# transmitter5r_eagle7x.net
KiCad netlist of a schematic drawn in EAGLE
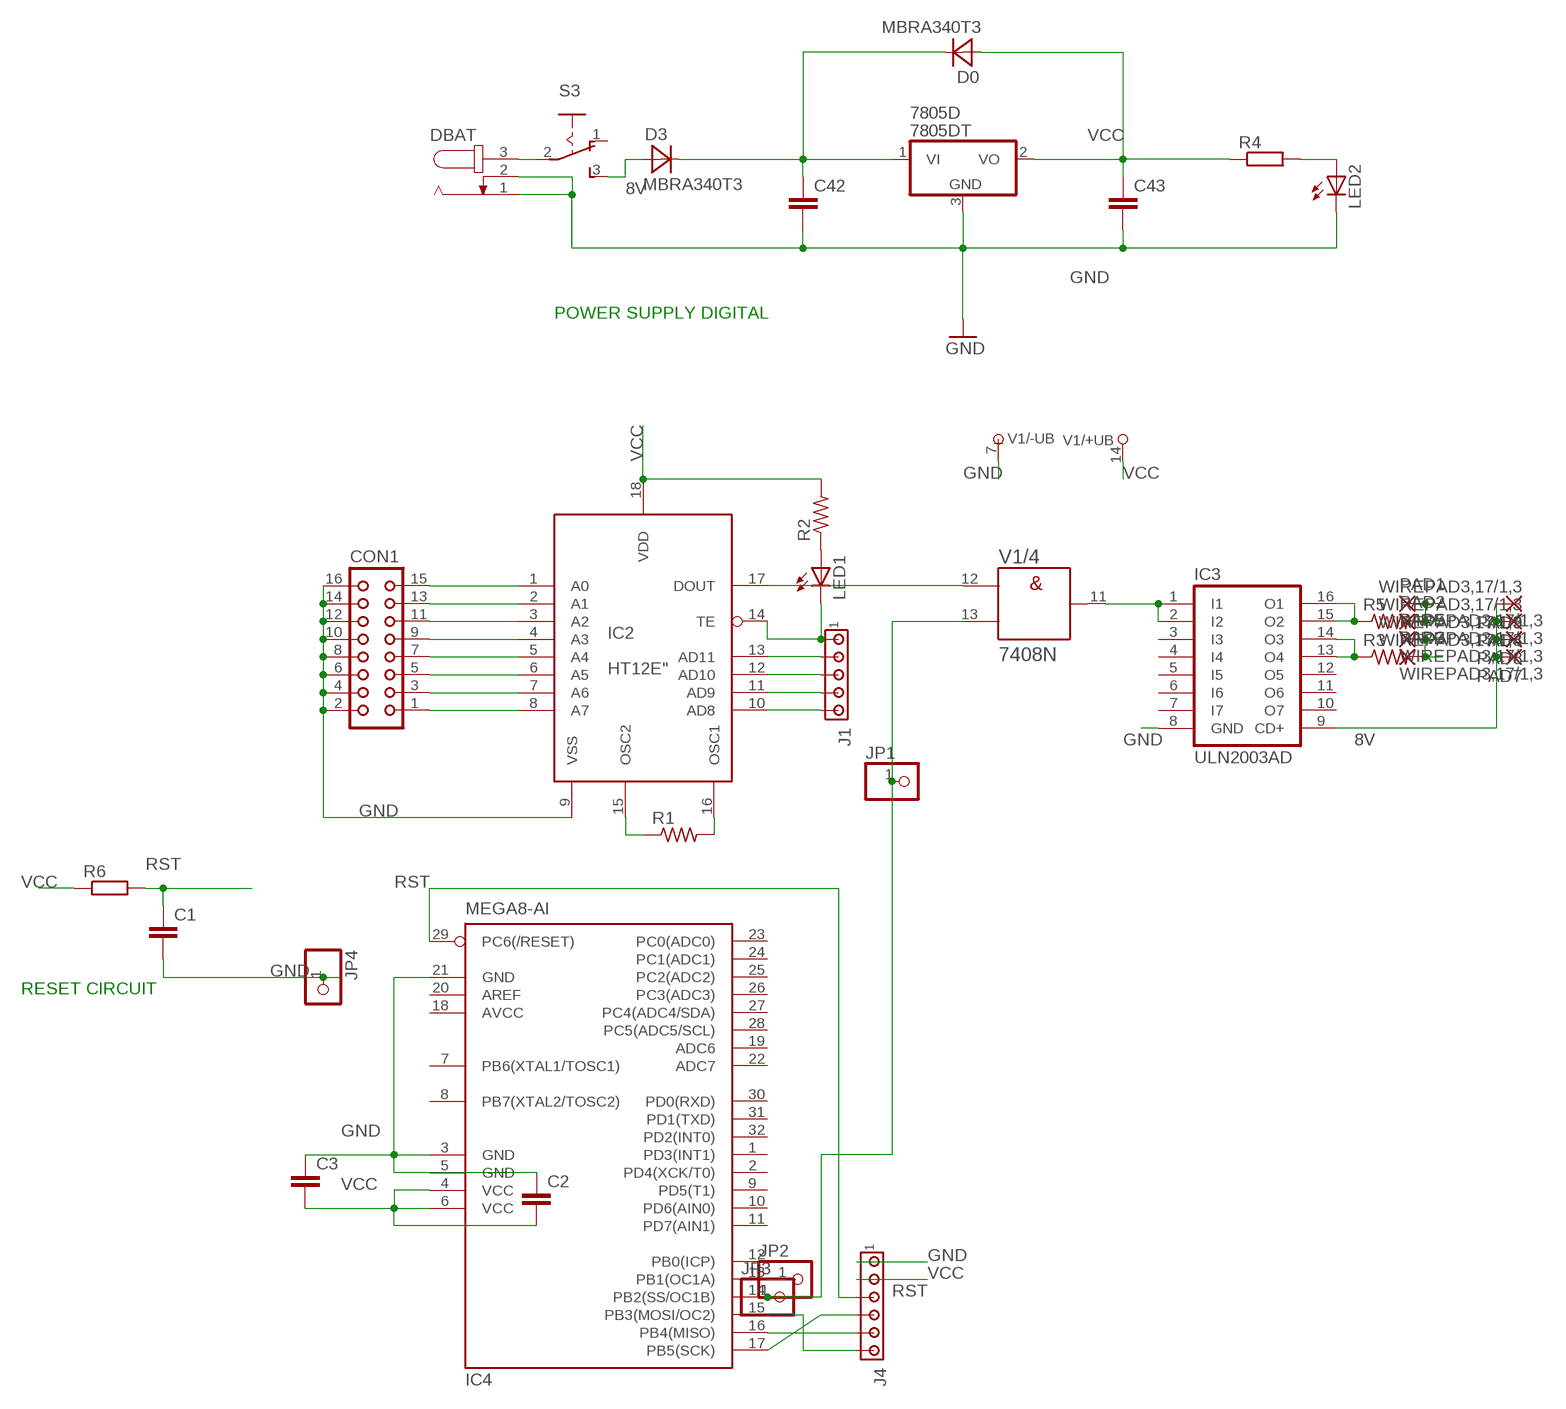
[diagram p0: schematic, sheet 1]

(export (version "E")
  (design (tool "Eeschema 10.0.6"))
  (components
    (comp (ref "7805D")
      (value "7805DT")
      (footprint "eagle-import:TO252")
      (libsource (lib "eagle-import") (part "78DT05"))
    )
    (comp (ref "C1")
      (value "C-EUC0603")
      (footprint "eagle-import:C0603")
      (libsource (lib "eagle-import") (part "C-EUC0603"))
    )
    (comp (ref "C2")
      (value "C-EUC0603")
      (footprint "eagle-import:C0603")
      (libsource (lib "eagle-import") (part "C-EUC0603"))
    )
    (comp (ref "C3")
      (value "C-EUC0603")
      (footprint "eagle-import:C0603")
      (libsource (lib "eagle-import") (part "C-EUC0603"))
    )
    (comp (ref "C42")
      (value "C-EUC0603")
      (footprint "eagle-import:C0603")
      (libsource (lib "eagle-import") (part "C-EUC0603"))
    )
    (comp (ref "C43")
      (value "C-EUC0603")
      (footprint "eagle-import:C0603")
      (libsource (lib "eagle-import") (part "C-EUC0603"))
    )
    (comp (ref "CON1")
      (value "CON16")
      (footprint "eagle-import:CON16")
      (libsource (lib "eagle-import") (part "CON16"))
    )
    (comp (ref "D0")
      (value "MBRA340T3")
      (footprint "eagle-import:SMA")
      (libsource (lib "eagle-import") (part "MBRA340T3"))
    )
    (comp (ref "D3")
      (value "MBRA340T3")
      (footprint "eagle-import:SMA")
      (libsource (lib "eagle-import") (part "MBRA340T3"))
    )
    (comp (ref "DBAT")
      (value "JACK-PLUG0")
      (footprint "eagle-import:SPC4077")
      (libsource (lib "eagle-import") (part "JACK-PLUG0"))
    )
    (comp (ref "IC2")
      (value "HT12E\"")
      (footprint "eagle-import:18-DIP-A")
      (libsource (lib "eagle-import") (part "HT12E{dblquote}"))
    )
    (comp (ref "IC3")
      (value "ULN2003AD")
      (footprint "eagle-import:SO16")
      (libsource (lib "eagle-import") (part "ULN2003AD"))
    )
    (comp (ref "IC4")
      (value "MEGA8-AI")
      (footprint "eagle-import:TQFP32-08")
      (libsource (lib "eagle-import") (part "MEGA8-AI"))
    )
    (comp (ref "J1")
      (value "MTA05-100")
      (footprint "eagle-import:10X05MTA")
      (libsource (lib "eagle-import") (part "MTA05-100"))
    )
    (comp (ref "J4")
      (value "MTA06-100")
      (footprint "eagle-import:10X06MTA")
      (libsource (lib "eagle-import") (part "MTA06-100"))
    )
    (comp (ref "JP1")
      (value "PINHD-1X1")
      (footprint "eagle-import:1X01")
      (libsource (lib "eagle-import") (part "PINHD-1X1"))
    )
    (comp (ref "JP2")
      (value "PINHD-1X1")
      (footprint "eagle-import:1X01")
      (libsource (lib "eagle-import") (part "PINHD-1X1"))
    )
    (comp (ref "JP3")
      (value "PINHD-1X1")
      (footprint "eagle-import:1X01")
      (libsource (lib "eagle-import") (part "PINHD-1X1"))
    )
    (comp (ref "JP4")
      (value "PINHD-1X1")
      (footprint "eagle-import:1X01")
      (libsource (lib "eagle-import") (part "PINHD-1X1"))
    )
    (comp (ref "LED1")
      (value "LED3MM")
      (footprint "eagle-import:LED3MM")
      (libsource (lib "eagle-import") (part "LED3MM"))
    )
    (comp (ref "LED2")
      (value "LED3MM")
      (footprint "eagle-import:LED3MM")
      (libsource (lib "eagle-import") (part "LED3MM"))
    )
    (comp (ref "PAD1")
      (value "WIREPAD3,17/1,3")
      (footprint "eagle-import:3,17_1,3")
      (libsource (lib "eagle-import") (part "WIREPAD3,17/1,3"))
    )
    (comp (ref "PAD2")
      (value "WIREPAD3,17/1,3")
      (footprint "eagle-import:3,17_1,3")
      (libsource (lib "eagle-import") (part "WIREPAD3,17/1,3"))
    )
    (comp (ref "PAD3")
      (value "WIREPAD3,17/1,3")
      (footprint "eagle-import:3,17_1,3")
      (libsource (lib "eagle-import") (part "WIREPAD3,17/1,3"))
    )
    (comp (ref "PAD4")
      (value "WIREPAD3,17/1,3")
      (footprint "eagle-import:3,17_1,3")
      (libsource (lib "eagle-import") (part "WIREPAD3,17/1,3"))
    )
    (comp (ref "PAD5")
      (value "WIREPAD3,17/1,3")
      (footprint "eagle-import:3,17_1,3")
      (libsource (lib "eagle-import") (part "WIREPAD3,17/1,3"))
    )
    (comp (ref "PAD7")
      (value "WIREPAD3,17/1,3")
      (footprint "eagle-import:3,17_1,3")
      (libsource (lib "eagle-import") (part "WIREPAD3,17/1,3"))
    )
    (comp (ref "PAD8")
      (value "WIREPAD3,17/1,3")
      (footprint "eagle-import:3,17_1,3")
      (libsource (lib "eagle-import") (part "WIREPAD3,17/1,3"))
    )
    (comp (ref "PAD9")
      (value "WIREPAD3,17/1,3")
      (footprint "eagle-import:3,17_1,3")
      (libsource (lib "eagle-import") (part "WIREPAD3,17/1,3"))
    )
    (comp (ref "R1")
      (value "R-US_VMTA55")
      (footprint "eagle-import:VMTA55")
      (libsource (lib "eagle-import") (part "R-US_VMTA55"))
    )
    (comp (ref "R2")
      (value "R-US_M1206")
      (footprint "eagle-import:M1206")
      (libsource (lib "eagle-import") (part "R-US_M1206"))
    )
    (comp (ref "R3")
      (value "R-US_0309/12")
      (footprint "eagle-import:0309_12")
      (libsource (lib "eagle-import") (part "R-US_0309/12"))
    )
    (comp (ref "R4")
      (value "R-EU_R0603")
      (footprint "eagle-import:R0603")
      (libsource (lib "eagle-import") (part "R-EU_R0603"))
    )
    (comp (ref "R5")
      (value "R-US_0309/12")
      (footprint "eagle-import:0309_12")
      (libsource (lib "eagle-import") (part "R-US_0309/12"))
    )
    (comp (ref "R6")
      (value "R-EU_R0603")
      (footprint "eagle-import:R0603")
      (libsource (lib "eagle-import") (part "R-EU_R0603"))
    )
    (comp (ref "S3")
      (value "255SB")
      (footprint "eagle-import:255SB")
      (libsource (lib "eagle-import") (part "255SB"))
    )
    (comp (ref "V1")
      (value "7408N")
      (footprint "eagle-import:DIL14")
      (libsource (lib "eagle-import") (part "7408N"))
    )
  )
  (nets
    (net (code "1") (name "/8V") (class "Default")
      (node (ref "D3") (pin "A") (pinfunction "A_A") (pintype "passive"))
      (node (ref "IC3") (pin "9") (pinfunction "CD+_9") (pintype "passive"))
      (node (ref "PAD4") (pin "1") (pinfunction "P_1") (pintype "passive"))
      (node (ref "PAD7") (pin "1") (pinfunction "P_1") (pintype "passive"))
      (node (ref "PAD8") (pin "1") (pinfunction "P_1") (pintype "passive"))
      (node (ref "PAD9") (pin "1") (pinfunction "P_1") (pintype "passive"))
      (node (ref "S3") (pin "3") (pinfunction "S_3") (pintype "passive"))
    )
    (net (code "2") (name "/AVCC") (class "Default")
      (node (ref "IC4") (pin "18") (pinfunction "AVCC_18") (pintype "power_in"))
    )
    (net (code "3") (name "/RST") (class "Default")
      (node (ref "C1") (pin "1") (pinfunction "1_1") (pintype "passive"))
      (node (ref "IC4") (pin "29") (pinfunction "PC6(/RESET)_29") (pintype "bidirectional"))
      (node (ref "J4") (pin "4") (pinfunction "3_4") (pintype "passive"))
      (node (ref "R6") (pin "2") (pinfunction "2_2") (pintype "passive"))
    )
    (net (code "4") (name "/VCC") (class "Default")
      (node (ref "7805D") (pin "2") (pinfunction "VO_2") (pintype "passive"))
      (node (ref "C2") (pin "2") (pinfunction "2_2") (pintype "passive"))
      (node (ref "C3") (pin "2") (pinfunction "2_2") (pintype "passive"))
      (node (ref "C43") (pin "1") (pinfunction "1_1") (pintype "passive"))
      (node (ref "D0") (pin "A") (pinfunction "A_A") (pintype "passive"))
      (node (ref "IC2") (pin "18") (pinfunction "VDD_18") (pintype "power_in"))
      (node (ref "IC4") (pin "4") (pinfunction "VCC_4") (pintype "power_in"))
      (node (ref "IC4") (pin "6") (pinfunction "VCC_6") (pintype "power_in"))
      (node (ref "J4") (pin "5") (pinfunction "2_5") (pintype "passive"))
      (node (ref "R2") (pin "2") (pinfunction "2_2") (pintype "passive"))
      (node (ref "R4") (pin "1") (pinfunction "1_1") (pintype "passive"))
      (node (ref "R6") (pin "1") (pinfunction "1_1") (pintype "passive"))
      (node (ref "V1") (pin "14") (pinfunction "+UB_14") (pintype "power_in"))
    )
    (net (code "5") (name "GND") (class "Default")
      (node (ref "7805D") (pin "3") (pinfunction "GND_3") (pintype "passive"))
      (node (ref "C1") (pin "2") (pinfunction "2_2") (pintype "passive"))
      (node (ref "C2") (pin "1") (pinfunction "1_1") (pintype "passive"))
      (node (ref "C3") (pin "1") (pinfunction "1_1") (pintype "passive"))
      (node (ref "C42") (pin "2") (pinfunction "2_2") (pintype "passive"))
      (node (ref "C43") (pin "2") (pinfunction "2_2") (pintype "passive"))
      (node (ref "CON1") (pin "10") (pinfunction "10_10") (pintype "passive"))
      (node (ref "CON1") (pin "12") (pinfunction "12_12") (pintype "passive"))
      (node (ref "CON1") (pin "14") (pinfunction "14_14") (pintype "passive"))
      (node (ref "CON1") (pin "16") (pinfunction "16_16") (pintype "passive"))
      (node (ref "CON1") (pin "2") (pinfunction "2_2") (pintype "passive"))
      (node (ref "CON1") (pin "4") (pinfunction "4_4") (pintype "passive"))
      (node (ref "CON1") (pin "6") (pinfunction "6_6") (pintype "passive"))
      (node (ref "CON1") (pin "8") (pinfunction "8_8") (pintype "passive"))
      (node (ref "DBAT") (pin "1") (pinfunction "1_1") (pintype "passive"))
      (node (ref "DBAT") (pin "2") (pinfunction "2_2") (pintype "passive"))
      (node (ref "IC2") (pin "9") (pinfunction "VSS_9") (pintype "power_in"))
      (node (ref "IC3") (pin "8") (pinfunction "GND_8") (pintype "power_in"))
      (node (ref "IC4") (pin "21") (pinfunction "GND_21") (pintype "power_in"))
      (node (ref "IC4") (pin "3") (pinfunction "GND_3") (pintype "power_in"))
      (node (ref "IC4") (pin "5") (pinfunction "GND_5") (pintype "power_in"))
      (node (ref "J4") (pin "6") (pinfunction "1_6") (pintype "passive"))
      (node (ref "JP4") (pin "1") (pinfunction "1_1") (pintype "passive"))
      (node (ref "LED2") (pin "K") (pinfunction "C_K") (pintype "passive"))
      (node (ref "V1") (pin "7") (pinfunction "-UB_7") (pintype "power_in"))
    )
    (net (code "6") (name "Net-(7805D-VI)") (class "Default")
      (node (ref "7805D") (pin "1") (pinfunction "VI_1") (pintype "input"))
      (node (ref "C42") (pin "1") (pinfunction "1_1") (pintype "passive"))
      (node (ref "D0") (pin "C") (pinfunction "C_C") (pintype "passive"))
      (node (ref "D3") (pin "C") (pinfunction "C_C") (pintype "passive"))
    )
    (net (code "7") (name "Net-(IC2-A0)") (class "Default")
      (node (ref "CON1") (pin "15") (pinfunction "15_15") (pintype "passive"))
      (node (ref "IC2") (pin "1") (pinfunction "A0_1") (pintype "input"))
    )
    (net (code "8") (name "Net-(IC2-A1)") (class "Default")
      (node (ref "CON1") (pin "13") (pinfunction "13_13") (pintype "passive"))
      (node (ref "IC2") (pin "2") (pinfunction "A1_2") (pintype "input"))
    )
    (net (code "9") (name "Net-(IC2-A2)") (class "Default")
      (node (ref "CON1") (pin "11") (pinfunction "11_11") (pintype "passive"))
      (node (ref "IC2") (pin "3") (pinfunction "A2_3") (pintype "input"))
    )
    (net (code "10") (name "Net-(IC2-A3)") (class "Default")
      (node (ref "CON1") (pin "9") (pinfunction "9_9") (pintype "passive"))
      (node (ref "IC2") (pin "4") (pinfunction "A3_4") (pintype "input"))
    )
    (net (code "11") (name "Net-(IC2-A4)") (class "Default")
      (node (ref "CON1") (pin "7") (pinfunction "7_7") (pintype "passive"))
      (node (ref "IC2") (pin "5") (pinfunction "A4_5") (pintype "input"))
    )
    (net (code "12") (name "Net-(IC2-A5)") (class "Default")
      (node (ref "CON1") (pin "5") (pinfunction "5_5") (pintype "passive"))
      (node (ref "IC2") (pin "6") (pinfunction "A5_6") (pintype "input"))
    )
    (net (code "13") (name "Net-(IC2-A6)") (class "Default")
      (node (ref "CON1") (pin "3") (pinfunction "3_3") (pintype "passive"))
      (node (ref "IC2") (pin "7") (pinfunction "A6_7") (pintype "input"))
    )
    (net (code "14") (name "Net-(IC2-A7)") (class "Default")
      (node (ref "CON1") (pin "1") (pinfunction "1_1") (pintype "passive"))
      (node (ref "IC2") (pin "8") (pinfunction "A7_8") (pintype "input"))
    )
    (net (code "15") (name "Net-(IC2-AD8)") (class "Default")
      (node (ref "IC2") (pin "10") (pinfunction "AD8_10") (pintype "input"))
      (node (ref "J1") (pin "5") (pinfunction "5_5") (pintype "passive"))
    )
    (net (code "16") (name "Net-(IC2-AD9)") (class "Default")
      (node (ref "IC2") (pin "11") (pinfunction "AD9_11") (pintype "input"))
      (node (ref "J1") (pin "4") (pinfunction "4_4") (pintype "passive"))
    )
    (net (code "17") (name "Net-(IC2-AD10)") (class "Default")
      (node (ref "IC2") (pin "12") (pinfunction "AD10_12") (pintype "input"))
      (node (ref "J1") (pin "3") (pinfunction "3_3") (pintype "passive"))
    )
    (net (code "18") (name "Net-(IC2-AD11)") (class "Default")
      (node (ref "IC2") (pin "13") (pinfunction "AD11_13") (pintype "input"))
      (node (ref "J1") (pin "2") (pinfunction "2_2") (pintype "passive"))
    )
    (net (code "19") (name "Net-(IC2-DOUT)") (class "Default")
      (node (ref "IC2") (pin "17") (pinfunction "DOUT_17") (pintype "output"))
      (node (ref "V1") (pin "12") (pinfunction "A_12") (pintype "input"))
    )
    (net (code "20") (name "Net-(IC2-OSC1)") (class "Default")
      (node (ref "IC2") (pin "16") (pinfunction "OSC1_16") (pintype "input"))
      (node (ref "R1") (pin "2") (pinfunction "2_2") (pintype "passive"))
    )
    (net (code "21") (name "Net-(IC2-OSC2)") (class "Default")
      (node (ref "IC2") (pin "15") (pinfunction "OSC2_15") (pintype "input"))
      (node (ref "R1") (pin "1") (pinfunction "1_1") (pintype "passive"))
    )
    (net (code "22") (name "Net-(IC2-TE)") (class "Default")
      (node (ref "IC2") (pin "14") (pinfunction "TE_14") (pintype "power_in"))
      (node (ref "J1") (pin "1") (pinfunction "1_1") (pintype "passive"))
      (node (ref "LED1") (pin "K") (pinfunction "C_K") (pintype "passive"))
    )
    (net (code "23") (name "Net-(IC3-I1)") (class "Default")
      (node (ref "IC3") (pin "1") (pinfunction "I1_1") (pintype "input"))
      (node (ref "IC3") (pin "2") (pinfunction "I2_2") (pintype "input"))
      (node (ref "V1") (pin "11") (pinfunction "Y_11") (pintype "output"))
    )
    (net (code "24") (name "Net-(IC3-O1)") (class "Default")
      (node (ref "IC3") (pin "15") (pinfunction "O2_15") (pintype "open_collector"))
      (node (ref "IC3") (pin "16") (pinfunction "O1_16") (pintype "open_collector"))
      (node (ref "R5") (pin "1") (pinfunction "1_1") (pintype "passive"))
    )
    (net (code "25") (name "Net-(IC3-O3)") (class "Default")
      (node (ref "IC3") (pin "13") (pinfunction "O4_13") (pintype "open_collector"))
      (node (ref "IC3") (pin "14") (pinfunction "O3_14") (pintype "open_collector"))
      (node (ref "R3") (pin "1") (pinfunction "1_1") (pintype "passive"))
    )
    (net (code "26") (name "Net-(IC4-PB1(OC1A))") (class "Default")
      (node (ref "IC4") (pin "13") (pinfunction "PB1(OC1A)_13") (pintype "bidirectional"))
      (node (ref "JP2") (pin "1") (pinfunction "1_1") (pintype "passive"))
    )
    (net (code "27") (name "Net-(IC4-PB2(SS{slash}OC1B))") (class "Default")
      (node (ref "IC4") (pin "14") (pinfunction "PB2(SS/OC1B)_14") (pintype "bidirectional"))
      (node (ref "JP1") (pin "1") (pinfunction "1_1") (pintype "passive"))
      (node (ref "JP3") (pin "1") (pinfunction "1_1") (pintype "passive"))
      (node (ref "V1") (pin "13") (pinfunction "B_13") (pintype "input"))
    )
    (net (code "28") (name "Net-(IC4-PB3(MOSI{slash}OC2))") (class "Default")
      (node (ref "IC4") (pin "15") (pinfunction "PB3(MOSI/OC2)_15") (pintype "bidirectional"))
      (node (ref "J4") (pin "1") (pinfunction "6_1") (pintype "passive"))
    )
    (net (code "29") (name "Net-(IC4-PB4(MISO))") (class "Default")
      (node (ref "IC4") (pin "16") (pinfunction "PB4(MISO)_16") (pintype "bidirectional"))
      (node (ref "J4") (pin "2") (pinfunction "5_2") (pintype "passive"))
    )
    (net (code "30") (name "Net-(IC4-PB5(SCK))") (class "Default")
      (node (ref "IC4") (pin "17") (pinfunction "PB5(SCK)_17") (pintype "bidirectional"))
      (node (ref "J4") (pin "3") (pinfunction "4_3") (pintype "passive"))
    )
    (net (code "31") (name "Net-(LED1-PadA)") (class "Default")
      (node (ref "LED1") (pin "A") (pinfunction "A_A") (pintype "passive"))
      (node (ref "R2") (pin "1") (pinfunction "1_1") (pintype "passive"))
    )
    (net (code "32") (name "Net-(LED2-PadA)") (class "Default")
      (node (ref "LED2") (pin "A") (pinfunction "A_A") (pintype "passive"))
      (node (ref "R4") (pin "2") (pinfunction "2_2") (pintype "passive"))
    )
    (net (code "33") (name "Net-(PAD1-P)") (class "Default")
      (node (ref "PAD1") (pin "1") (pinfunction "P_1") (pintype "passive"))
      (node (ref "PAD2") (pin "1") (pinfunction "P_1") (pintype "passive"))
      (node (ref "R5") (pin "2") (pinfunction "2_2") (pintype "passive"))
    )
    (net (code "34") (name "Net-(PAD3-P)") (class "Default")
      (node (ref "PAD3") (pin "1") (pinfunction "P_1") (pintype "passive"))
      (node (ref "PAD5") (pin "1") (pinfunction "P_1") (pintype "passive"))
      (node (ref "R3") (pin "2") (pinfunction "2_2") (pintype "passive"))
    )
    (net (code "35") (name "Net-(S3-P)") (class "Default")
      (node (ref "DBAT") (pin "3") (pinfunction "3_3") (pintype "passive"))
      (node (ref "S3") (pin "2") (pinfunction "P_2") (pintype "passive"))
    )
    (net (code "36") (name "unconnected-(IC3-I3-Pad3)") (class "Default")
      (node (ref "IC3") (pin "3") (pinfunction "I3_3") (pintype "input"))
    )
    (net (code "37") (name "unconnected-(IC3-I4-Pad4)") (class "Default")
      (node (ref "IC3") (pin "4") (pinfunction "I4_4") (pintype "input"))
    )
    (net (code "38") (name "unconnected-(IC3-I5-Pad5)") (class "Default")
      (node (ref "IC3") (pin "5") (pinfunction "I5_5") (pintype "input"))
    )
    (net (code "39") (name "unconnected-(IC3-I6-Pad6)") (class "Default")
      (node (ref "IC3") (pin "6") (pinfunction "I6_6") (pintype "input"))
    )
    (net (code "40") (name "unconnected-(IC3-I7-Pad7)") (class "Default")
      (node (ref "IC3") (pin "7") (pinfunction "I7_7") (pintype "input"))
    )
    (net (code "41") (name "unconnected-(IC3-O5-Pad12)") (class "Default")
      (node (ref "IC3") (pin "12") (pinfunction "O5_12") (pintype "open_collector"))
    )
    (net (code "42") (name "unconnected-(IC3-O6-Pad11)") (class "Default")
      (node (ref "IC3") (pin "11") (pinfunction "O6_11") (pintype "open_collector"))
    )
    (net (code "43") (name "unconnected-(IC3-O7-Pad10)") (class "Default")
      (node (ref "IC3") (pin "10") (pinfunction "O7_10") (pintype "open_collector"))
    )
    (net (code "44") (name "unconnected-(IC4-ADC6-Pad19)") (class "Default")
      (node (ref "IC4") (pin "19") (pinfunction "ADC6_19") (pintype "bidirectional"))
    )
    (net (code "45") (name "unconnected-(IC4-ADC7-Pad22)") (class "Default")
      (node (ref "IC4") (pin "22") (pinfunction "ADC7_22") (pintype "bidirectional"))
    )
    (net (code "46") (name "unconnected-(IC4-AREF-Pad20)") (class "Default")
      (node (ref "IC4") (pin "20") (pinfunction "AREF_20") (pintype "passive"))
    )
    (net (code "47") (name "unconnected-(IC4-PB0(ICP)-Pad12)") (class "Default")
      (node (ref "IC4") (pin "12") (pinfunction "PB0(ICP)_12") (pintype "bidirectional"))
    )
    (net (code "48") (name "unconnected-(IC4-PB6(XTAL1{slash}TOSC1)-Pad7)") (class "Default")
      (node (ref "IC4") (pin "7") (pinfunction "PB6(XTAL1/TOSC1)_7") (pintype "bidirectional"))
    )
    (net (code "49") (name "unconnected-(IC4-PB7(XTAL2{slash}TOSC2)-Pad8)") (class "Default")
      (node (ref "IC4") (pin "8") (pinfunction "PB7(XTAL2/TOSC2)_8") (pintype "bidirectional"))
    )
    (net (code "50") (name "unconnected-(IC4-PC0(ADC0)-Pad23)") (class "Default")
      (node (ref "IC4") (pin "23") (pinfunction "PC0(ADC0)_23") (pintype "bidirectional"))
    )
    (net (code "51") (name "unconnected-(IC4-PC1(ADC1)-Pad24)") (class "Default")
      (node (ref "IC4") (pin "24") (pinfunction "PC1(ADC1)_24") (pintype "bidirectional"))
    )
    (net (code "52") (name "unconnected-(IC4-PC2(ADC2)-Pad25)") (class "Default")
      (node (ref "IC4") (pin "25") (pinfunction "PC2(ADC2)_25") (pintype "bidirectional"))
    )
    (net (code "53") (name "unconnected-(IC4-PC3(ADC3)-Pad26)") (class "Default")
      (node (ref "IC4") (pin "26") (pinfunction "PC3(ADC3)_26") (pintype "bidirectional"))
    )
    (net (code "54") (name "unconnected-(IC4-PC4(ADC4{slash}SDA)-Pad27)") (class "Default")
      (node (ref "IC4") (pin "27") (pinfunction "PC4(ADC4/SDA)_27") (pintype "bidirectional"))
    )
    (net (code "55") (name "unconnected-(IC4-PC5(ADC5{slash}SCL)-Pad28)") (class "Default")
      (node (ref "IC4") (pin "28") (pinfunction "PC5(ADC5/SCL)_28") (pintype "bidirectional"))
    )
    (net (code "56") (name "unconnected-(IC4-PD0(RXD)-Pad30)") (class "Default")
      (node (ref "IC4") (pin "30") (pinfunction "PD0(RXD)_30") (pintype "bidirectional"))
    )
    (net (code "57") (name "unconnected-(IC4-PD1(TXD)-Pad31)") (class "Default")
      (node (ref "IC4") (pin "31") (pinfunction "PD1(TXD)_31") (pintype "bidirectional"))
    )
    (net (code "58") (name "unconnected-(IC4-PD2(INT0)-Pad32)") (class "Default")
      (node (ref "IC4") (pin "32") (pinfunction "PD2(INT0)_32") (pintype "bidirectional"))
    )
    (net (code "59") (name "unconnected-(IC4-PD3(INT1)-Pad1)") (class "Default")
      (node (ref "IC4") (pin "1") (pinfunction "PD3(INT1)_1") (pintype "bidirectional"))
    )
    (net (code "60") (name "unconnected-(IC4-PD4(XCK{slash}T0)-Pad2)") (class "Default")
      (node (ref "IC4") (pin "2") (pinfunction "PD4(XCK/T0)_2") (pintype "bidirectional"))
    )
    (net (code "61") (name "unconnected-(IC4-PD5(T1)-Pad9)") (class "Default")
      (node (ref "IC4") (pin "9") (pinfunction "PD5(T1)_9") (pintype "bidirectional"))
    )
    (net (code "62") (name "unconnected-(IC4-PD6(AIN0)-Pad10)") (class "Default")
      (node (ref "IC4") (pin "10") (pinfunction "PD6(AIN0)_10") (pintype "bidirectional"))
    )
    (net (code "63") (name "unconnected-(IC4-PD7(AIN1)-Pad11)") (class "Default")
      (node (ref "IC4") (pin "11") (pinfunction "PD7(AIN1)_11") (pintype "bidirectional"))
    )
    (net (code "64") (name "unconnected-(S3-O-Pad1)") (class "Default")
      (node (ref "S3") (pin "1") (pinfunction "O_1") (pintype "passive"))
    )
  )
)
